# micro_schematic.net
KiCad netlist of a schematic drawn in Altium Designer
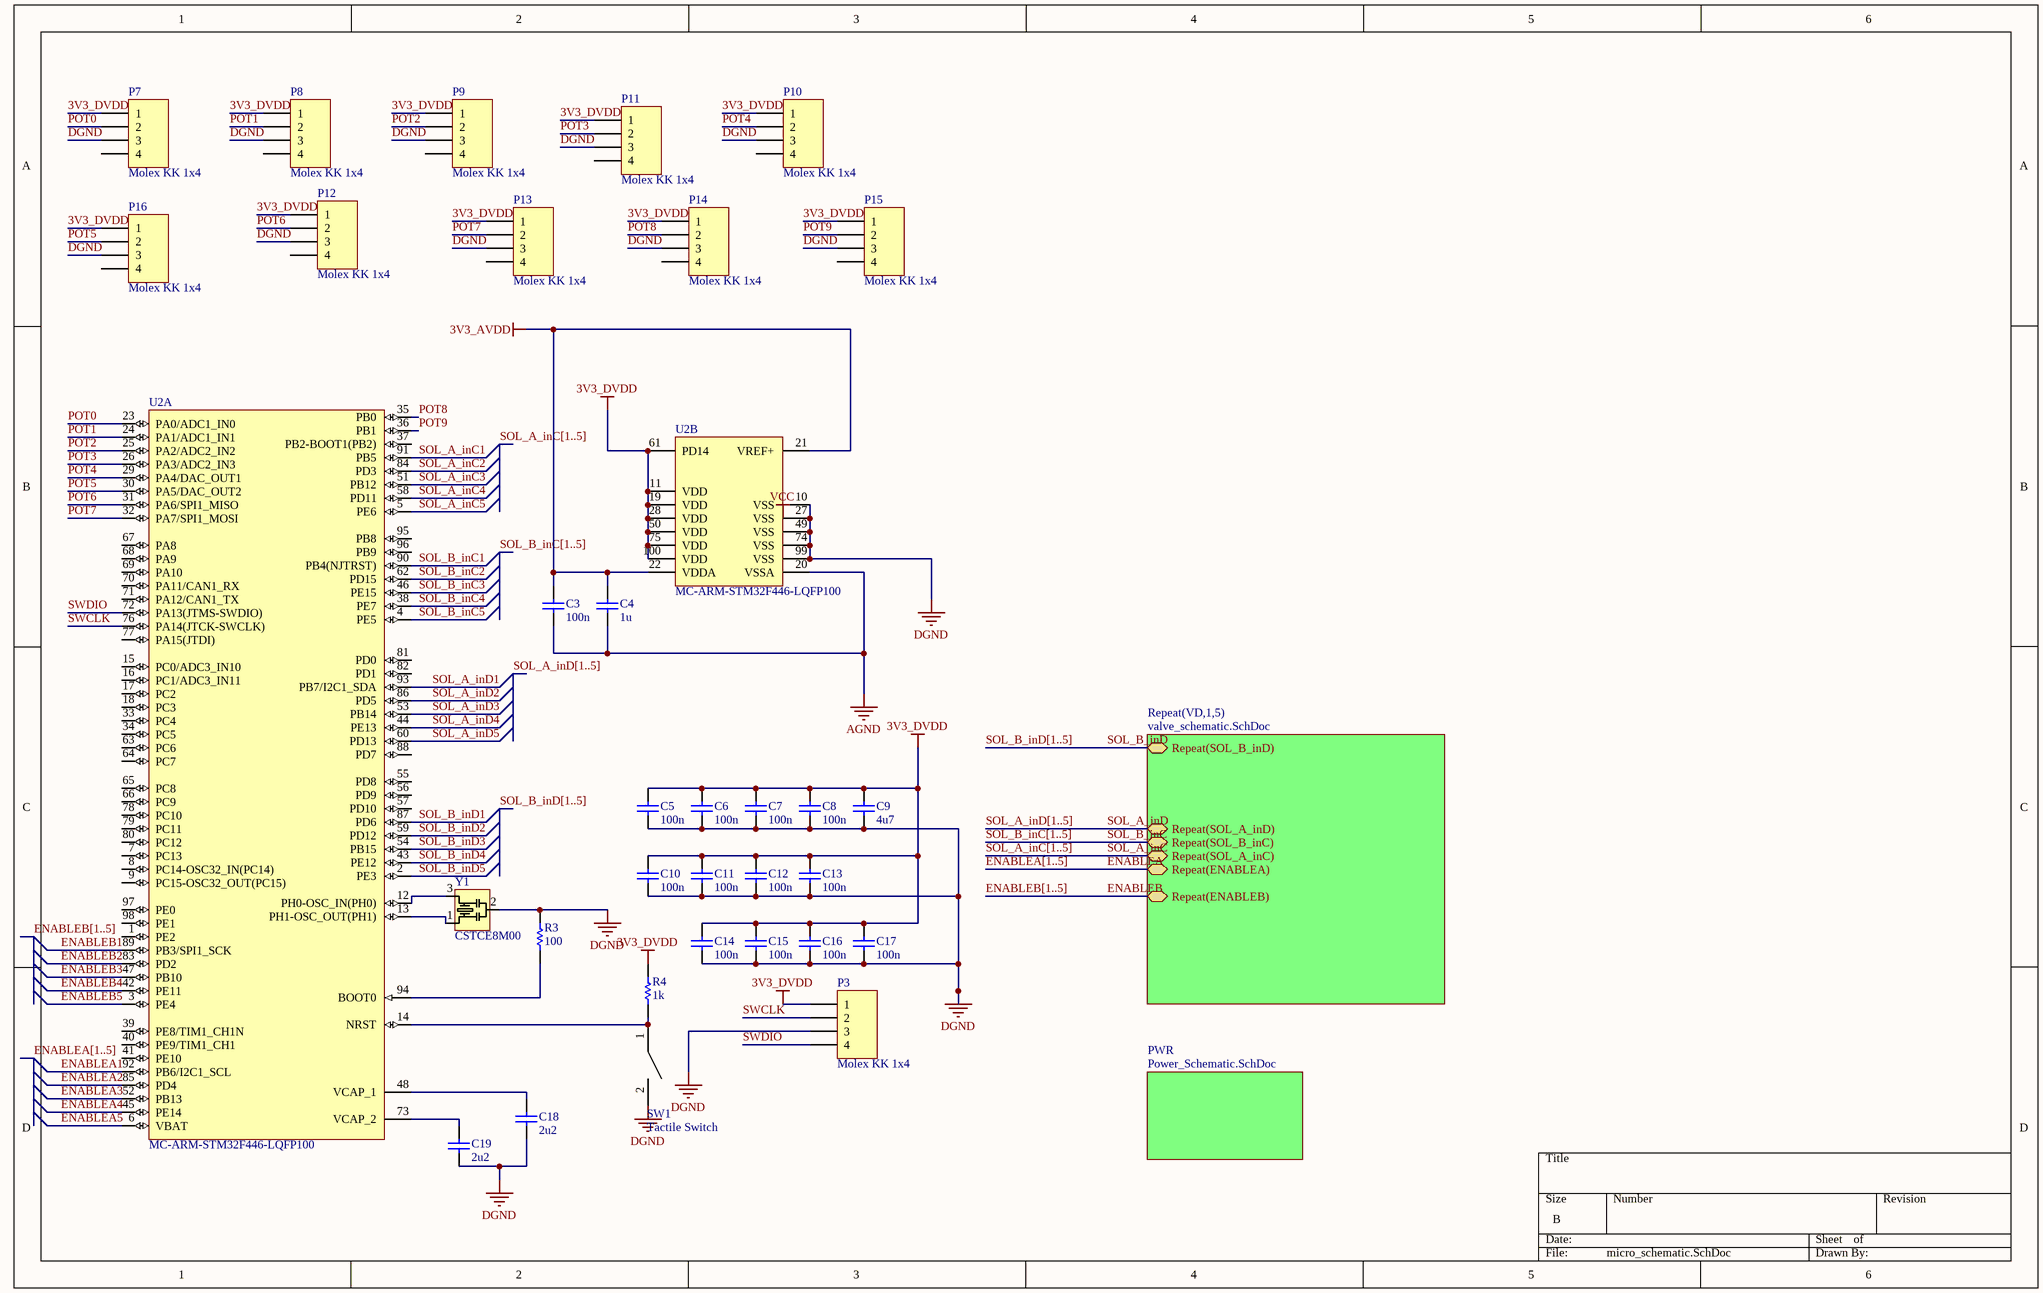
[diagram p0: micro_schematic.SchDoc]

(export (version "E")
  (design (tool "Eeschema 10.0.6"))
  (components
    (comp (ref "C3")
      (value "100n")
      (footprint "C0603")
      (description "0603 Capacitor")
      (libsource (lib "PARSEC") (part "C0603"))
    )
    (comp (ref "C4")
      (value "1u")
      (footprint "C0603")
      (description "0603 Capacitor")
      (libsource (lib "PARSEC") (part "C0603"))
    )
    (comp (ref "C5")
      (value "100n")
      (footprint "C0805")
      (description "0805 Capacitor")
      (libsource (lib "PARSEC") (part "C0805"))
    )
    (comp (ref "C6")
      (value "100n")
      (footprint "C0805")
      (description "0805 Capacitor")
      (libsource (lib "PARSEC") (part "C0805"))
    )
    (comp (ref "C7")
      (value "100n")
      (footprint "C0805")
      (description "0805 Capacitor")
      (libsource (lib "PARSEC") (part "C0805"))
    )
    (comp (ref "C8")
      (value "100n")
      (footprint "C0805")
      (description "0805 Capacitor")
      (libsource (lib "PARSEC") (part "C0805"))
    )
    (comp (ref "C9")
      (value "4u7")
      (footprint "C0805")
      (description "0805 Capacitor")
      (libsource (lib "PARSEC") (part "C0805"))
    )
    (comp (ref "C10")
      (value "100n")
      (footprint "C0805")
      (description "0805 Capacitor")
      (libsource (lib "PARSEC") (part "C0805"))
    )
    (comp (ref "C11")
      (value "100n")
      (footprint "C0805")
      (description "0805 Capacitor")
      (libsource (lib "PARSEC") (part "C0805"))
    )
    (comp (ref "C12")
      (value "100n")
      (footprint "C0805")
      (description "0805 Capacitor")
      (libsource (lib "PARSEC") (part "C0805"))
    )
    (comp (ref "C13")
      (value "100n")
      (footprint "C0805")
      (description "0805 Capacitor")
      (libsource (lib "PARSEC") (part "C0805"))
    )
    (comp (ref "C14")
      (value "100n")
      (footprint "C0805")
      (description "0805 Capacitor")
      (libsource (lib "PARSEC") (part "C0805"))
    )
    (comp (ref "C15")
      (value "100n")
      (footprint "C0805")
      (description "0805 Capacitor")
      (libsource (lib "PARSEC") (part "C0805"))
    )
    (comp (ref "C16")
      (value "100n")
      (footprint "C0805")
      (description "0805 Capacitor")
      (libsource (lib "PARSEC") (part "C0805"))
    )
    (comp (ref "C17")
      (value "100n")
      (footprint "C0805")
      (description "0805 Capacitor")
      (libsource (lib "PARSEC") (part "C0805"))
    )
    (comp (ref "C18")
      (value "2u2")
      (footprint "C0603")
      (description "0603 Capacitor")
      (libsource (lib "PARSEC") (part "C0603"))
    )
    (comp (ref "C19")
      (value "2u2")
      (footprint "C0603")
      (description "0603 Capacitor")
      (libsource (lib "PARSEC") (part "C0603"))
    )
    (comp (ref "P3")
      (value "Molex KK 1x4")
      (footprint "Molex KK 4x1")
      (description "1x4 Molex KK Connector")
      (libsource (lib "PARSEC") (part "Molex KK 1x4"))
    )
    (comp (ref "P7")
      (value "Molex KK 1x4")
      (footprint "Molex KK 4x1")
      (description "1x4 Molex KK Connector")
      (libsource (lib "PARSEC") (part "Molex KK 1x4"))
    )
    (comp (ref "P8")
      (value "Molex KK 1x4")
      (footprint "Molex KK 4x1")
      (description "1x4 Molex KK Connector")
      (libsource (lib "PARSEC") (part "Molex KK 1x4"))
    )
    (comp (ref "P9")
      (value "Molex KK 1x4")
      (footprint "Molex KK 4x1")
      (description "1x4 Molex KK Connector")
      (libsource (lib "PARSEC") (part "Molex KK 1x4"))
    )
    (comp (ref "P10")
      (value "Molex KK 1x4")
      (footprint "Molex KK 4x1")
      (description "1x4 Molex KK Connector")
      (libsource (lib "PARSEC") (part "Molex KK 1x4"))
    )
    (comp (ref "P11")
      (value "Molex KK 1x4")
      (footprint "Molex KK 4x1")
      (description "1x4 Molex KK Connector")
      (libsource (lib "PARSEC") (part "Molex KK 1x4"))
    )
    (comp (ref "P12")
      (value "Molex KK 1x4")
      (footprint "Molex KK 4x1")
      (description "1x4 Molex KK Connector")
      (libsource (lib "PARSEC") (part "Molex KK 1x4"))
    )
    (comp (ref "P13")
      (value "Molex KK 1x4")
      (footprint "Molex KK 4x1")
      (description "1x4 Molex KK Connector")
      (libsource (lib "PARSEC") (part "Molex KK 1x4"))
    )
    (comp (ref "P14")
      (value "Molex KK 1x4")
      (footprint "Molex KK 4x1")
      (description "1x4 Molex KK Connector")
      (libsource (lib "PARSEC") (part "Molex KK 1x4"))
    )
    (comp (ref "P15")
      (value "Molex KK 1x4")
      (footprint "Molex KK 4x1")
      (description "1x4 Molex KK Connector")
      (libsource (lib "PARSEC") (part "Molex KK 1x4"))
    )
    (comp (ref "P16")
      (value "Molex KK 1x4")
      (footprint "Molex KK 4x1")
      (description "1x4 Molex KK Connector")
      (libsource (lib "PARSEC") (part "Molex KK 1x4"))
    )
    (comp (ref "R3")
      (value "100")
      (footprint "R0805")
      (description "RESISTOR 0805")
      (libsource (lib "PARSEC") (part "R0805"))
    )
    (comp (ref "R4")
      (value "1k")
      (footprint "R0805")
      (description "RESISTOR 0805")
      (libsource (lib "PARSEC") (part "R0805"))
    )
    (comp (ref "SW1")
      (value "Tactile Switch")
      (footprint "Tactile Switch")
      (description "TL3301AF160QG")
      (libsource (lib "PARSEC") (part "Tactile Switch"))
    )
    (comp (ref "U2")
      (value "MC-ARM-STM32F446-LQFP100")
      (footprint "STM-LQFP100_N")
      (libsource (lib "") (part "MC-ARM-STM32F446-LQFP100_1"))
    )
    (comp (ref "Y1")
      (value "CSTCE8M00")
      (footprint "8MHz Ceramic Resonator")
      (description "8MHz Ceramic Resonator")
      (libsource (lib "PARSEC") (part "CSTCE8M00"))
    )
  )
  (nets
    (net (code "2") (name "/ENABLEA1") (class "Default")
      (node (ref "U2") (pin "92") (pinfunction "PB6/I2C1_SCL_92") (pintype "bidirectional"))
    )
    (net (code "3") (name "/ENABLEA2") (class "Default")
      (node (ref "U2") (pin "85") (pinfunction "PD4_85") (pintype "bidirectional"))
    )
    (net (code "4") (name "/ENABLEA3") (class "Default")
      (node (ref "U2") (pin "52") (pinfunction "PB13_52") (pintype "bidirectional"))
    )
    (net (code "5") (name "/ENABLEA4") (class "Default")
      (node (ref "U2") (pin "45") (pinfunction "PE14_45") (pintype "bidirectional"))
    )
    (net (code "6") (name "/ENABLEA5") (class "Default")
      (node (ref "U2") (pin "6") (pinfunction "VBAT_6") (pintype "bidirectional"))
    )
    (net (code "9") (name "/ENABLEB1") (class "Default")
      (node (ref "U2") (pin "89") (pinfunction "PB3/SPI1_SCK_89") (pintype "bidirectional"))
    )
    (net (code "10") (name "/ENABLEB2") (class "Default")
      (node (ref "U2") (pin "83") (pinfunction "PD2_83") (pintype "bidirectional"))
    )
    (net (code "11") (name "/ENABLEB3") (class "Default")
      (node (ref "U2") (pin "47") (pinfunction "PB10_47") (pintype "bidirectional"))
    )
    (net (code "12") (name "/ENABLEB4") (class "Default")
      (node (ref "U2") (pin "42") (pinfunction "PE11_42") (pintype "bidirectional"))
    )
    (net (code "13") (name "/ENABLEB5") (class "Default")
      (node (ref "U2") (pin "3") (pinfunction "PE4_3") (pintype "bidirectional"))
    )
    (net (code "15") (name "/POT0") (class "Default")
      (node (ref "P7") (pin "2") (pinfunction "2_2") (pintype "passive"))
      (node (ref "U2") (pin "23") (pinfunction "PA0/ADC1_IN0_23") (pintype "bidirectional"))
    )
    (net (code "16") (name "/POT1") (class "Default")
      (node (ref "P8") (pin "2") (pinfunction "2_2") (pintype "passive"))
      (node (ref "U2") (pin "24") (pinfunction "PA1/ADC1_IN1_24") (pintype "bidirectional"))
    )
    (net (code "17") (name "/POT2") (class "Default")
      (node (ref "P9") (pin "2") (pinfunction "2_2") (pintype "passive"))
      (node (ref "U2") (pin "25") (pinfunction "PA2/ADC2_IN2_25") (pintype "bidirectional"))
    )
    (net (code "18") (name "/POT3") (class "Default")
      (node (ref "P11") (pin "2") (pinfunction "2_2") (pintype "passive"))
      (node (ref "U2") (pin "26") (pinfunction "PA3/ADC2_IN3_26") (pintype "bidirectional"))
    )
    (net (code "19") (name "/POT4") (class "Default")
      (node (ref "P10") (pin "2") (pinfunction "2_2") (pintype "passive"))
      (node (ref "U2") (pin "29") (pinfunction "PA4/DAC_OUT1_29") (pintype "bidirectional"))
    )
    (net (code "20") (name "/POT5") (class "Default")
      (node (ref "P16") (pin "2") (pinfunction "2_2") (pintype "passive"))
      (node (ref "U2") (pin "30") (pinfunction "PA5/DAC_OUT2_30") (pintype "bidirectional"))
    )
    (net (code "21") (name "/POT6") (class "Default")
      (node (ref "P12") (pin "2") (pinfunction "2_2") (pintype "passive"))
      (node (ref "U2") (pin "31") (pinfunction "PA6/SPI1_MISO_31") (pintype "bidirectional"))
    )
    (net (code "22") (name "/POT7") (class "Default")
      (node (ref "P13") (pin "2") (pinfunction "2_2") (pintype "passive"))
      (node (ref "U2") (pin "32") (pinfunction "PA7/SPI1_MOSI_32") (pintype "bidirectional"))
    )
    (net (code "23") (name "/POT8") (class "Default")
      (node (ref "P14") (pin "2") (pinfunction "2_2") (pintype "passive"))
      (node (ref "U2") (pin "35") (pinfunction "PB0_35") (pintype "bidirectional"))
    )
    (net (code "24") (name "/POT9") (class "Default")
      (node (ref "P15") (pin "2") (pinfunction "2_2") (pintype "passive"))
      (node (ref "U2") (pin "36") (pinfunction "PB1_36") (pintype "bidirectional"))
    )
    (net (code "26") (name "/SOL_A_inC1") (class "Default")
      (node (ref "U2") (pin "91") (pinfunction "PB5_91") (pintype "bidirectional"))
    )
    (net (code "27") (name "/SOL_A_inC2") (class "Default")
      (node (ref "U2") (pin "84") (pinfunction "PD3_84") (pintype "bidirectional"))
    )
    (net (code "28") (name "/SOL_A_inC3") (class "Default")
      (node (ref "U2") (pin "51") (pinfunction "PB12_51") (pintype "bidirectional"))
    )
    (net (code "29") (name "/SOL_A_inC4") (class "Default")
      (node (ref "U2") (pin "58") (pinfunction "PD11_58") (pintype "bidirectional"))
    )
    (net (code "30") (name "/SOL_A_inC5") (class "Default")
      (node (ref "U2") (pin "5") (pinfunction "PE6_5") (pintype "bidirectional"))
    )
    (net (code "33") (name "/SOL_A_inD1") (class "Default")
      (node (ref "U2") (pin "93") (pinfunction "PB7/I2C1_SDA_93") (pintype "bidirectional"))
    )
    (net (code "34") (name "/SOL_A_inD2") (class "Default")
      (node (ref "U2") (pin "86") (pinfunction "PD5_86") (pintype "bidirectional"))
    )
    (net (code "35") (name "/SOL_A_inD3") (class "Default")
      (node (ref "U2") (pin "53") (pinfunction "PB14_53") (pintype "bidirectional"))
    )
    (net (code "36") (name "/SOL_A_inD4") (class "Default")
      (node (ref "U2") (pin "44") (pinfunction "PE13_44") (pintype "bidirectional"))
    )
    (net (code "37") (name "/SOL_A_inD5") (class "Default")
      (node (ref "U2") (pin "60") (pinfunction "PD13_60") (pintype "bidirectional"))
    )
    (net (code "40") (name "/SOL_B_inC1") (class "Default")
      (node (ref "U2") (pin "90") (pinfunction "PB4(NJTRST)_90") (pintype "bidirectional"))
    )
    (net (code "41") (name "/SOL_B_inC2") (class "Default")
      (node (ref "U2") (pin "62") (pinfunction "PD15_62") (pintype "bidirectional"))
    )
    (net (code "42") (name "/SOL_B_inC3") (class "Default")
      (node (ref "U2") (pin "46") (pinfunction "PE15_46") (pintype "bidirectional"))
    )
    (net (code "43") (name "/SOL_B_inC4") (class "Default")
      (node (ref "U2") (pin "38") (pinfunction "PE7_38") (pintype "bidirectional"))
    )
    (net (code "44") (name "/SOL_B_inC5") (class "Default")
      (node (ref "U2") (pin "4") (pinfunction "PE5_4") (pintype "bidirectional"))
    )
    (net (code "47") (name "/SOL_B_inD1") (class "Default")
      (node (ref "U2") (pin "87") (pinfunction "PD6_87") (pintype "bidirectional"))
    )
    (net (code "48") (name "/SOL_B_inD2") (class "Default")
      (node (ref "U2") (pin "59") (pinfunction "PD12_59") (pintype "bidirectional"))
    )
    (net (code "49") (name "/SOL_B_inD3") (class "Default")
      (node (ref "U2") (pin "54") (pinfunction "PB15_54") (pintype "bidirectional"))
    )
    (net (code "50") (name "/SOL_B_inD4") (class "Default")
      (node (ref "U2") (pin "43") (pinfunction "PE12_43") (pintype "bidirectional"))
    )
    (net (code "51") (name "/SOL_B_inD5") (class "Default")
      (node (ref "U2") (pin "2") (pinfunction "PE3_2") (pintype "bidirectional"))
    )
    (net (code "53") (name "/SWCLK") (class "Default")
      (node (ref "P3") (pin "2") (pinfunction "2_2") (pintype "passive"))
      (node (ref "U2") (pin "76") (pinfunction "PA14(JTCK-SWCLK)_76") (pintype "bidirectional"))
    )
    (net (code "54") (name "/SWDIO") (class "Default")
      (node (ref "P3") (pin "4") (pinfunction "4_4") (pintype "passive"))
      (node (ref "U2") (pin "72") (pinfunction "PA13(JTMS-SWDIO)_72") (pintype "bidirectional"))
    )
    (net (code "55") (name "3V3_AVDD") (class "Default")
      (node (ref "C3") (pin "1") (pinfunction "1_1") (pintype "passive"))
      (node (ref "C4") (pin "1") (pinfunction "1_1") (pintype "passive"))
      (node (ref "U2") (pin "21") (pinfunction "VREF+_21") (pintype "power_in"))
      (node (ref "U2") (pin "22") (pinfunction "VDDA_22") (pintype "power_in"))
    )
    (net (code "56") (name "3V3_DVDD") (class "Default")
      (node (ref "C10") (pin "1") (pinfunction "1_1") (pintype "passive"))
      (node (ref "C11") (pin "1") (pinfunction "1_1") (pintype "passive"))
      (node (ref "C12") (pin "1") (pinfunction "1_1") (pintype "passive"))
      (node (ref "C13") (pin "1") (pinfunction "1_1") (pintype "passive"))
      (node (ref "C14") (pin "1") (pinfunction "1_1") (pintype "passive"))
      (node (ref "C15") (pin "1") (pinfunction "1_1") (pintype "passive"))
      (node (ref "C16") (pin "1") (pinfunction "1_1") (pintype "passive"))
      (node (ref "C17") (pin "1") (pinfunction "1_1") (pintype "passive"))
      (node (ref "C5") (pin "1") (pinfunction "1_1") (pintype "passive"))
      (node (ref "C6") (pin "1") (pinfunction "1_1") (pintype "passive"))
      (node (ref "C7") (pin "1") (pinfunction "1_1") (pintype "passive"))
      (node (ref "C8") (pin "1") (pinfunction "1_1") (pintype "passive"))
      (node (ref "C9") (pin "1") (pinfunction "1_1") (pintype "passive"))
      (node (ref "P10") (pin "1") (pinfunction "1_1") (pintype "passive"))
      (node (ref "P11") (pin "1") (pinfunction "1_1") (pintype "passive"))
      (node (ref "P12") (pin "1") (pinfunction "1_1") (pintype "passive"))
      (node (ref "P13") (pin "1") (pinfunction "1_1") (pintype "passive"))
      (node (ref "P14") (pin "1") (pinfunction "1_1") (pintype "passive"))
      (node (ref "P15") (pin "1") (pinfunction "1_1") (pintype "passive"))
      (node (ref "P16") (pin "1") (pinfunction "1_1") (pintype "passive"))
      (node (ref "P3") (pin "1") (pinfunction "1_1") (pintype "passive"))
      (node (ref "P7") (pin "1") (pinfunction "1_1") (pintype "passive"))
      (node (ref "P8") (pin "1") (pinfunction "1_1") (pintype "passive"))
      (node (ref "P9") (pin "1") (pinfunction "1_1") (pintype "passive"))
      (node (ref "R4") (pin "2") (pinfunction "2_2") (pintype "passive"))
      (node (ref "U2") (pin "100") (pinfunction "VDD_100") (pintype "power_in"))
      (node (ref "U2") (pin "11") (pinfunction "VDD_11") (pintype "power_in"))
      (node (ref "U2") (pin "19") (pinfunction "VDD_19") (pintype "power_in"))
      (node (ref "U2") (pin "28") (pinfunction "VDD_28") (pintype "power_in"))
      (node (ref "U2") (pin "50") (pinfunction "VDD_50") (pintype "power_in"))
      (node (ref "U2") (pin "61") (pinfunction "PD14_61") (pintype "power_in"))
      (node (ref "U2") (pin "75") (pinfunction "VDD_75") (pintype "power_in"))
    )
    (net (code "57") (name "AGND") (class "Default")
      (node (ref "C3") (pin "2") (pinfunction "2_2") (pintype "passive"))
      (node (ref "C4") (pin "2") (pinfunction "2_2") (pintype "passive"))
      (node (ref "U2") (pin "20") (pinfunction "VSSA_20") (pintype "power_in"))
    )
    (net (code "58") (name "DGND") (class "Default")
      (node (ref "C10") (pin "2") (pinfunction "2_2") (pintype "passive"))
      (node (ref "C11") (pin "2") (pinfunction "2_2") (pintype "passive"))
      (node (ref "C12") (pin "2") (pinfunction "2_2") (pintype "passive"))
      (node (ref "C13") (pin "2") (pinfunction "2_2") (pintype "passive"))
      (node (ref "C14") (pin "2") (pinfunction "2_2") (pintype "passive"))
      (node (ref "C15") (pin "2") (pinfunction "2_2") (pintype "passive"))
      (node (ref "C16") (pin "2") (pinfunction "2_2") (pintype "passive"))
      (node (ref "C17") (pin "2") (pinfunction "2_2") (pintype "passive"))
      (node (ref "C18") (pin "2") (pinfunction "2_2") (pintype "passive"))
      (node (ref "C19") (pin "2") (pinfunction "2_2") (pintype "passive"))
      (node (ref "C5") (pin "2") (pinfunction "2_2") (pintype "passive"))
      (node (ref "C6") (pin "2") (pinfunction "2_2") (pintype "passive"))
      (node (ref "C7") (pin "2") (pinfunction "2_2") (pintype "passive"))
      (node (ref "C8") (pin "2") (pinfunction "2_2") (pintype "passive"))
      (node (ref "C9") (pin "2") (pinfunction "2_2") (pintype "passive"))
      (node (ref "P10") (pin "3") (pinfunction "3_3") (pintype "passive"))
      (node (ref "P11") (pin "3") (pinfunction "3_3") (pintype "passive"))
      (node (ref "P12") (pin "3") (pinfunction "3_3") (pintype "passive"))
      (node (ref "P13") (pin "3") (pinfunction "3_3") (pintype "passive"))
      (node (ref "P14") (pin "3") (pinfunction "3_3") (pintype "passive"))
      (node (ref "P15") (pin "3") (pinfunction "3_3") (pintype "passive"))
      (node (ref "P16") (pin "3") (pinfunction "3_3") (pintype "passive"))
      (node (ref "P3") (pin "3") (pinfunction "3_3") (pintype "passive"))
      (node (ref "P7") (pin "3") (pinfunction "3_3") (pintype "passive"))
      (node (ref "P8") (pin "3") (pinfunction "3_3") (pintype "passive"))
      (node (ref "P9") (pin "3") (pinfunction "3_3") (pintype "passive"))
      (node (ref "R3") (pin "2") (pinfunction "2_2") (pintype "passive"))
      (node (ref "U2") (pin "10") (pinfunction "VSS_10") (pintype "power_in"))
      (node (ref "U2") (pin "27") (pinfunction "VSS_27") (pintype "power_in"))
      (node (ref "U2") (pin "49") (pinfunction "VSS_49") (pintype "power_in"))
      (node (ref "U2") (pin "74") (pinfunction "VSS_74") (pintype "power_in"))
      (node (ref "U2") (pin "99") (pinfunction "VSS_99") (pintype "power_in"))
      (node (ref "Y1") (pin "2") (pinfunction "GND_2") (pintype "passive"))
    )
    (net (code "59") (name "Net-(U2A-BOOT0)") (class "Default")
      (node (ref "R3") (pin "1") (pinfunction "1_1") (pintype "passive"))
      (node (ref "U2") (pin "94") (pinfunction "BOOT0_94") (pintype "input"))
    )
    (net (code "60") (name "Net-(U2A-NRST)") (class "Default")
      (node (ref "R4") (pin "1") (pinfunction "1_1") (pintype "passive"))
      (node (ref "SW1") (pin "1") (pinfunction "1_1") (pintype "passive"))
      (node (ref "U2") (pin "14") (pinfunction "NRST_14") (pintype "bidirectional"))
    )
    (net (code "61") (name "Net-(U2A-PH0-OSC_IN(PH0))") (class "Default")
      (node (ref "U2") (pin "12") (pinfunction "PH0-OSC_IN(PH0)_12") (pintype "bidirectional"))
      (node (ref "Y1") (pin "3") (pinfunction "OSC2_3") (pintype "passive"))
    )
    (net (code "62") (name "Net-(U2A-PH1-OSC_OUT(PH1))") (class "Default")
      (node (ref "U2") (pin "13") (pinfunction "PH1-OSC_OUT(PH1)_13") (pintype "bidirectional"))
      (node (ref "Y1") (pin "1") (pinfunction "OSC1_1") (pintype "passive"))
    )
    (net (code "63") (name "Net-(U2A-VCAP_1)") (class "Default")
      (node (ref "C18") (pin "1") (pinfunction "1_1") (pintype "passive"))
      (node (ref "U2") (pin "48") (pinfunction "VCAP_1_48") (pintype "passive"))
    )
    (net (code "64") (name "Net-(U2A-VCAP_2)") (class "Default")
      (node (ref "C19") (pin "1") (pinfunction "1_1") (pintype "passive"))
      (node (ref "U2") (pin "73") (pinfunction "VCAP_2_73") (pintype "passive"))
    )
    (net (code "66") (name "unconnected-(P7-Pad4)") (class "Default")
      (node (ref "P7") (pin "4") (pinfunction "4_4") (pintype "passive"))
    )
    (net (code "67") (name "unconnected-(P8-Pad4)") (class "Default")
      (node (ref "P8") (pin "4") (pinfunction "4_4") (pintype "passive"))
    )
    (net (code "68") (name "unconnected-(P9-Pad4)") (class "Default")
      (node (ref "P9") (pin "4") (pinfunction "4_4") (pintype "passive"))
    )
    (net (code "69") (name "unconnected-(P10-Pad4)") (class "Default")
      (node (ref "P10") (pin "4") (pinfunction "4_4") (pintype "passive"))
    )
    (net (code "70") (name "unconnected-(P11-Pad4)") (class "Default")
      (node (ref "P11") (pin "4") (pinfunction "4_4") (pintype "passive"))
    )
    (net (code "71") (name "unconnected-(P12-Pad4)") (class "Default")
      (node (ref "P12") (pin "4") (pinfunction "4_4") (pintype "passive"))
    )
    (net (code "72") (name "unconnected-(P13-Pad4)") (class "Default")
      (node (ref "P13") (pin "4") (pinfunction "4_4") (pintype "passive"))
    )
    (net (code "73") (name "unconnected-(P14-Pad4)") (class "Default")
      (node (ref "P14") (pin "4") (pinfunction "4_4") (pintype "passive"))
    )
    (net (code "74") (name "unconnected-(P15-Pad4)") (class "Default")
      (node (ref "P15") (pin "4") (pinfunction "4_4") (pintype "passive"))
    )
    (net (code "75") (name "unconnected-(P16-Pad4)") (class "Default")
      (node (ref "P16") (pin "4") (pinfunction "4_4") (pintype "passive"))
    )
    (net (code "76") (name "unconnected-(SW1-1-Pad2)") (class "Default")
      (node (ref "SW1") (pin "2") (pinfunction "1_2") (pintype "passive"))
    )
    (net (code "77") (name "unconnected-(U2A-PA8-Pad67)") (class "Default")
      (node (ref "U2") (pin "67") (pinfunction "PA8_67") (pintype "bidirectional"))
    )
    (net (code "78") (name "unconnected-(U2A-PA9-Pad68)") (class "Default")
      (node (ref "U2") (pin "68") (pinfunction "PA9_68") (pintype "bidirectional"))
    )
    (net (code "79") (name "unconnected-(U2A-PA10-Pad69)") (class "Default")
      (node (ref "U2") (pin "69") (pinfunction "PA10_69") (pintype "bidirectional"))
    )
    (net (code "80") (name "unconnected-(U2A-PA11{slash}CAN1_RX-Pad70)") (class "Default")
      (node (ref "U2") (pin "70") (pinfunction "PA11/CAN1_RX_70") (pintype "bidirectional"))
    )
    (net (code "81") (name "unconnected-(U2A-PA12{slash}CAN1_TX-Pad71)") (class "Default")
      (node (ref "U2") (pin "71") (pinfunction "PA12/CAN1_TX_71") (pintype "bidirectional"))
    )
    (net (code "82") (name "unconnected-(U2A-PA15(JTDI)-Pad77)") (class "Default")
      (node (ref "U2") (pin "77") (pinfunction "PA15(JTDI)_77") (pintype "bidirectional"))
    )
    (net (code "83") (name "unconnected-(U2A-PB2-BOOT1(PB2)-Pad37)") (class "Default")
      (node (ref "U2") (pin "37") (pinfunction "PB2-BOOT1(PB2)_37") (pintype "bidirectional"))
    )
    (net (code "84") (name "unconnected-(U2A-PB8-Pad95)") (class "Default")
      (node (ref "U2") (pin "95") (pinfunction "PB8_95") (pintype "bidirectional"))
    )
    (net (code "85") (name "unconnected-(U2A-PB9-Pad96)") (class "Default")
      (node (ref "U2") (pin "96") (pinfunction "PB9_96") (pintype "bidirectional"))
    )
    (net (code "86") (name "unconnected-(U2A-PC0{slash}ADC3_IN10-Pad15)") (class "Default")
      (node (ref "U2") (pin "15") (pinfunction "PC0/ADC3_IN10_15") (pintype "bidirectional"))
    )
    (net (code "87") (name "unconnected-(U2A-PC1{slash}ADC3_IN11-Pad16)") (class "Default")
      (node (ref "U2") (pin "16") (pinfunction "PC1/ADC3_IN11_16") (pintype "bidirectional"))
    )
    (net (code "88") (name "unconnected-(U2A-PC2-Pad17)") (class "Default")
      (node (ref "U2") (pin "17") (pinfunction "PC2_17") (pintype "bidirectional"))
    )
    (net (code "89") (name "unconnected-(U2A-PC3-Pad18)") (class "Default")
      (node (ref "U2") (pin "18") (pinfunction "PC3_18") (pintype "bidirectional"))
    )
    (net (code "90") (name "unconnected-(U2A-PC4-Pad33)") (class "Default")
      (node (ref "U2") (pin "33") (pinfunction "PC4_33") (pintype "bidirectional"))
    )
    (net (code "91") (name "unconnected-(U2A-PC5-Pad34)") (class "Default")
      (node (ref "U2") (pin "34") (pinfunction "PC5_34") (pintype "bidirectional"))
    )
    (net (code "92") (name "unconnected-(U2A-PC6-Pad63)") (class "Default")
      (node (ref "U2") (pin "63") (pinfunction "PC6_63") (pintype "bidirectional"))
    )
    (net (code "93") (name "unconnected-(U2A-PC7-Pad64)") (class "Default")
      (node (ref "U2") (pin "64") (pinfunction "PC7_64") (pintype "bidirectional"))
    )
    (net (code "94") (name "unconnected-(U2A-PC8-Pad65)") (class "Default")
      (node (ref "U2") (pin "65") (pinfunction "PC8_65") (pintype "bidirectional"))
    )
    (net (code "95") (name "unconnected-(U2A-PC9-Pad66)") (class "Default")
      (node (ref "U2") (pin "66") (pinfunction "PC9_66") (pintype "bidirectional"))
    )
    (net (code "96") (name "unconnected-(U2A-PC10-Pad78)") (class "Default")
      (node (ref "U2") (pin "78") (pinfunction "PC10_78") (pintype "bidirectional"))
    )
    (net (code "97") (name "unconnected-(U2A-PC11-Pad79)") (class "Default")
      (node (ref "U2") (pin "79") (pinfunction "PC11_79") (pintype "bidirectional"))
    )
    (net (code "98") (name "unconnected-(U2A-PC12-Pad80)") (class "Default")
      (node (ref "U2") (pin "80") (pinfunction "PC12_80") (pintype "bidirectional"))
    )
    (net (code "99") (name "unconnected-(U2A-PC13-Pad7)") (class "Default")
      (node (ref "U2") (pin "7") (pinfunction "PC13_7") (pintype "bidirectional"))
    )
    (net (code "100") (name "unconnected-(U2A-PC14-OSC32_IN(PC14)-Pad8)") (class "Default")
      (node (ref "U2") (pin "8") (pinfunction "PC14-OSC32_IN(PC14)_8") (pintype "bidirectional"))
    )
    (net (code "101") (name "unconnected-(U2A-PC15-OSC32_OUT(PC15)-Pad9)") (class "Default")
      (node (ref "U2") (pin "9") (pinfunction "PC15-OSC32_OUT(PC15)_9") (pintype "bidirectional"))
    )
    (net (code "102") (name "unconnected-(U2A-PD0-Pad81)") (class "Default")
      (node (ref "U2") (pin "81") (pinfunction "PD0_81") (pintype "bidirectional"))
    )
    (net (code "103") (name "unconnected-(U2A-PD1-Pad82)") (class "Default")
      (node (ref "U2") (pin "82") (pinfunction "PD1_82") (pintype "bidirectional"))
    )
    (net (code "104") (name "unconnected-(U2A-PD7-Pad88)") (class "Default")
      (node (ref "U2") (pin "88") (pinfunction "PD7_88") (pintype "bidirectional"))
    )
    (net (code "105") (name "unconnected-(U2A-PD8-Pad55)") (class "Default")
      (node (ref "U2") (pin "55") (pinfunction "PD8_55") (pintype "bidirectional"))
    )
    (net (code "106") (name "unconnected-(U2A-PD9-Pad56)") (class "Default")
      (node (ref "U2") (pin "56") (pinfunction "PD9_56") (pintype "bidirectional"))
    )
    (net (code "107") (name "unconnected-(U2A-PD10-Pad57)") (class "Default")
      (node (ref "U2") (pin "57") (pinfunction "PD10_57") (pintype "bidirectional"))
    )
    (net (code "108") (name "unconnected-(U2A-PE0-Pad97)") (class "Default")
      (node (ref "U2") (pin "97") (pinfunction "PE0_97") (pintype "bidirectional"))
    )
    (net (code "109") (name "unconnected-(U2A-PE1-Pad98)") (class "Default")
      (node (ref "U2") (pin "98") (pinfunction "PE1_98") (pintype "bidirectional"))
    )
    (net (code "110") (name "unconnected-(U2A-PE2-Pad1)") (class "Default")
      (node (ref "U2") (pin "1") (pinfunction "PE2_1") (pintype "bidirectional"))
    )
    (net (code "111") (name "unconnected-(U2A-PE8{slash}TIM1_CH1N-Pad39)") (class "Default")
      (node (ref "U2") (pin "39") (pinfunction "PE8/TIM1_CH1N_39") (pintype "bidirectional"))
    )
    (net (code "112") (name "unconnected-(U2A-PE9{slash}TIM1_CH1-Pad40)") (class "Default")
      (node (ref "U2") (pin "40") (pinfunction "PE9/TIM1_CH1_40") (pintype "bidirectional"))
    )
    (net (code "113") (name "unconnected-(U2A-PE10-Pad41)") (class "Default")
      (node (ref "U2") (pin "41") (pinfunction "PE10_41") (pintype "bidirectional"))
    )
  )
)
